# Shema_ele.net
KiCad netlist of a schematic drawn in Altium Designer
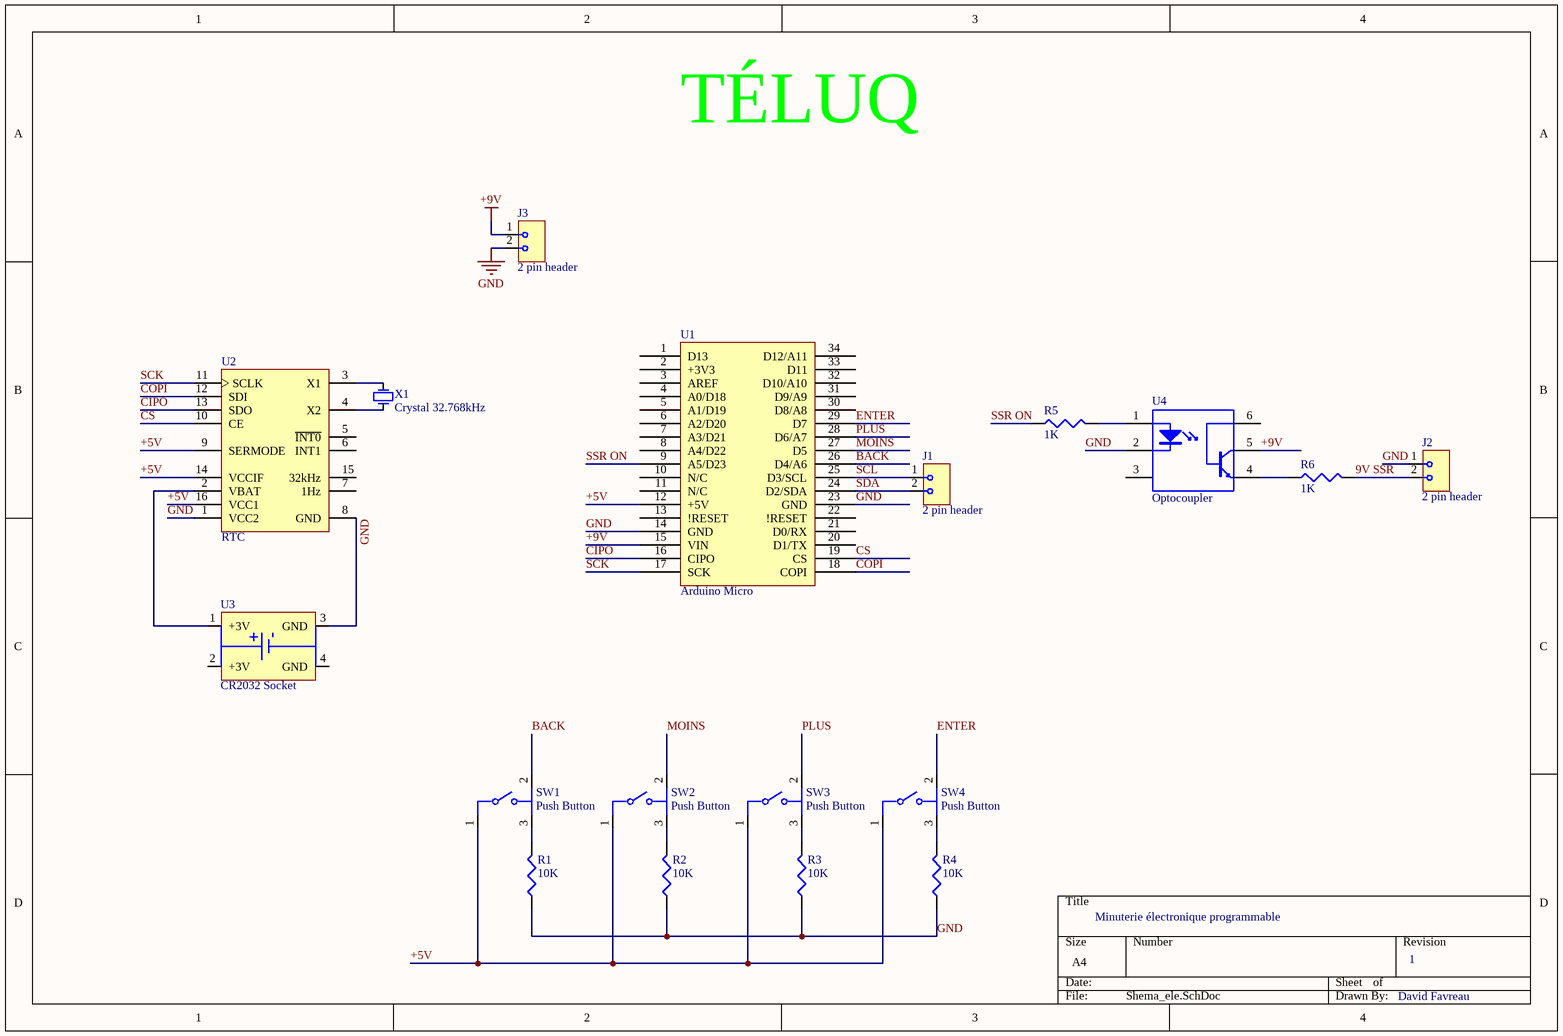
[diagram p0: Shema_ele.SchDoc]

(export (version "E")
  (design (tool "Eeschema 10.0.6"))
  (components
    (comp (ref "*")
      (value "Logo TELUQ")
      (footprint "Logo TELQUQ")
      (libsource (lib "Minuterie_SCH") (part "Logo TELUQ"))
    )
    (comp (ref "J1")
      (value "2 pin header")
      (footprint "Dual header")
      (description "2.54mm (0.1\") Pitch SIL Vertical PC Tail Pin Header, 6.1mm mating pin height, tin, 2 contacts")
      (fields (field (name "MANUFACTURER") "Harwin") (field (name "MANUFACTURER PART NUMBER") "M20-9990246"))
      (libsource (lib "Minuterie_SCH") (part "M20-9990246"))
    )
    (comp (ref "J2")
      (value "2 pin header")
      (footprint "Dual header")
      (description "2.54mm (0.1\") Pitch SIL Vertical PC Tail Pin Header, 6.1mm mating pin height, tin, 2 contacts")
      (fields (field (name "MANUFACTURER") "Harwin") (field (name "MANUFACTURER PART NUMBER") "M20-9990246"))
      (libsource (lib "Minuterie_SCH") (part "M20-9990246"))
    )
    (comp (ref "J3")
      (value "2 pin header")
      (footprint "Dual header")
      (description "2.54mm (0.1\") Pitch SIL Vertical PC Tail Pin Header, 6.1mm mating pin height, tin, 2 contacts")
      (fields (field (name "MANUFACTURER") "Harwin") (field (name "MANUFACTURER PART NUMBER") "M20-9990246"))
      (libsource (lib "Minuterie_SCH") (part "M20-9990246"))
    )
    (comp (ref "R1")
      (value "10K")
      (footprint "Res_TH")
      (description "Res Metal Film 10K Ohm 1% 1/4W ±100ppm/°C Conformal Axial Thru-Hole T/R")
      (fields
        (field (name "MANUFACTURER") "Yageo")
        (field (name "MANUFACTURER PART NUMBER") "MFR-25FRF52-10K")
      )
      (libsource (lib "Minuterie_SCH") (part "MFR-25FRF52-10K"))
    )
    (comp (ref "R2")
      (value "10K")
      (footprint "Res_TH")
      (description "Res Metal Film 10K Ohm 1% 1/4W ±100ppm/°C Conformal Axial Thru-Hole T/R")
      (fields
        (field (name "MANUFACTURER") "Yageo")
        (field (name "MANUFACTURER PART NUMBER") "MFR-25FRF52-10K")
      )
      (libsource (lib "Minuterie_SCH") (part "MFR-25FRF52-10K"))
    )
    (comp (ref "R3")
      (value "10K")
      (footprint "Res_TH")
      (description "Res Metal Film 10K Ohm 1% 1/4W ±100ppm/°C Conformal Axial Thru-Hole T/R")
      (fields
        (field (name "MANUFACTURER") "Yageo")
        (field (name "MANUFACTURER PART NUMBER") "MFR-25FRF52-10K")
      )
      (libsource (lib "Minuterie_SCH") (part "MFR-25FRF52-10K"))
    )
    (comp (ref "R4")
      (value "10K")
      (footprint "Res_TH")
      (description "Res Metal Film 10K Ohm 1% 1/4W ±100ppm/°C Conformal Axial Thru-Hole T/R")
      (fields
        (field (name "MANUFACTURER") "Yageo")
        (field (name "MANUFACTURER PART NUMBER") "MFR-25FRF52-10K")
      )
      (libsource (lib "Minuterie_SCH") (part "MFR-25FRF52-10K"))
    )
    (comp (ref "R5")
      (value "1K")
      (footprint "Res_TH")
      (description "Res Metal Film 1K Ohm 1% 0.25W(1/4W) ±100ppm/C AXL Automotive T/R")
      (fields
        (field (name "MANUFACTURER") "Yageo")
        (field (name "MANUFACTURER PART NUMBER") "MFR-25FRF52-1K")
      )
      (libsource (lib "Minuterie_SCH") (part "MFR-25FRF52-1K"))
    )
    (comp (ref "R6")
      (value "1K")
      (footprint "Res_TH")
      (description "Res Metal Film 1K Ohm 1% 0.25W(1/4W) ±100ppm/C AXL Automotive T/R")
      (fields
        (field (name "MANUFACTURER") "Yageo")
        (field (name "MANUFACTURER PART NUMBER") "MFR-25FRF52-1K")
      )
      (libsource (lib "Minuterie_SCH") (part "MFR-25FRF52-1K"))
    )
    (comp (ref "SW1")
      (value "Push Button")
      (footprint "Push button")
      (description "Switch Tactile OFF (ON) SPST Round Button PC Pins 0.05A 24VDC 1.57N Thru-Hole Loose")
      (fields
        (field (name "MANUFACTURER") "TE Connectivity Alcoswitch")
        (field (name "MANUFACTURER PART NUMBER") "FSM103")
      )
      (libsource (lib "Minuterie_SCH") (part "FSM103"))
    )
    (comp (ref "SW2")
      (value "Push Button")
      (footprint "Push button")
      (description "Switch Tactile OFF (ON) SPST Round Button PC Pins 0.05A 24VDC 1.57N Thru-Hole Loose")
      (fields
        (field (name "MANUFACTURER") "TE Connectivity Alcoswitch")
        (field (name "MANUFACTURER PART NUMBER") "FSM103")
      )
      (libsource (lib "Minuterie_SCH") (part "FSM103"))
    )
    (comp (ref "SW3")
      (value "Push Button")
      (footprint "Push button")
      (description "Switch Tactile OFF (ON) SPST Round Button PC Pins 0.05A 24VDC 1.57N Thru-Hole Loose")
      (fields
        (field (name "MANUFACTURER") "TE Connectivity Alcoswitch")
        (field (name "MANUFACTURER PART NUMBER") "FSM103")
      )
      (libsource (lib "Minuterie_SCH") (part "FSM103"))
    )
    (comp (ref "SW4")
      (value "Push Button")
      (footprint "Push button")
      (description "Switch Tactile OFF (ON) SPST Round Button PC Pins 0.05A 24VDC 1.57N Thru-Hole Loose")
      (fields
        (field (name "MANUFACTURER") "TE Connectivity Alcoswitch")
        (field (name "MANUFACTURER PART NUMBER") "FSM103")
      )
      (libsource (lib "Minuterie_SCH") (part "FSM103"))
    )
    (comp (ref "U1")
      (value "Arduino Micro")
      (footprint "Micro-C")
      (description "ATmega32u4 Microcontroller Micro Development Board 16MHz CPU 2.5KB RAM 1KB/32KB EEPROM/Flash")
      (fields (field (name "MANUFACTURER") "Arduino") (field (name "MANUFACTURER PART NUMBER") "A000053"))
      (libsource (lib "Minuterie_SCH") (part "A000053"))
    )
    (comp (ref "U2")
      (value "RTC")
      (footprint "DIP16")
      (description "DS1306 Series 2 to 5.5 V 96B Battery-Backed NV RAM Serial Alarm RTC - DIP-16")
      (fields (field (name "MANUFACTURER") "Maxim") (field (name "MANUFACTURER PART NUMBER") "DS1306N+"))
      (libsource (lib "Minuterie_SCH") (part "DS1306N+"))
    )
    (comp (ref "U3")
      (value "CR2032 Socket")
      (footprint "Battery socket")
      (description "Heyco RDD Lockit Strain Relief Bushings Straight-Thru RDD 101A BLACK")
      (fields
        (field (name "MANUFACTURER") "Adafruit Industries")
        (field (name "MANUFACTURER PART NUMBER") "1870")
      )
      (libsource (lib "Minuterie_SCH") (part "1870"))
    )
    (comp (ref "U4")
      (value "Optocoupler")
      (footprint "DIP6")
      (description "Single Channel 80 V 5000 Vrms Phototransistor Optocoupler Through Hole - DIP-6")
      (fields (field (name "MANUFACTURER") "Vishay") (field (name "MANUFACTURER PART NUMBER") "4N35"))
      (libsource (lib "Minuterie_SCH") (part "4N35"))
    )
    (comp (ref "X1")
      (value "Crystal 32.768kHz")
      (footprint "Crystal")
      (description "Crystal 0.032768MHz ±20ppm (Tol) 6pF Flexural 35000Ohm 2-Pin Thru-Hole Bulk")
      (fields
        (field (name "MANUFACTURER") "Citizen")
        (field (name "MANUFACTURER PART NUMBER") "CFS-20632768DZBB")
      )
      (libsource (lib "Minuterie_SCH") (part "CFS-20632768DZBB"))
    )
  )
  (nets
    (net (code "1") (name "+9V") (class "Default")
      (node (ref "J3") (pin "1") (pinfunction "1_1") (pintype "passive"))
      (node (ref "U1") (pin "15") (pinfunction "VIN_15") (pintype "passive"))
      (node (ref "U4") (pin "5") (pinfunction "C_5") (pintype "passive"))
    )
    (net (code "2") (name "/+5V") (class "Default")
      (node (ref "SW1") (pin "1") (pinfunction "1_1") (pintype "passive"))
      (node (ref "SW2") (pin "1") (pinfunction "1_1") (pintype "passive"))
      (node (ref "SW3") (pin "1") (pinfunction "1_1") (pintype "passive"))
      (node (ref "SW4") (pin "1") (pinfunction "1_1") (pintype "passive"))
      (node (ref "U1") (pin "12") (pinfunction "+5V_12") (pintype "passive"))
      (node (ref "U2") (pin "14") (pinfunction "VCCIF_14") (pintype "power_in"))
      (node (ref "U2") (pin "16") (pinfunction "VCC1_16") (pintype "power_in"))
      (node (ref "U2") (pin "9") (pinfunction "SERMODE_9") (pintype "passive"))
    )
    (net (code "3") (name "/9V SSR") (class "Default")
      (node (ref "J2") (pin "2") (pinfunction "2_2") (pintype "passive"))
      (node (ref "R6") (pin "2") (pinfunction "2_2") (pintype "passive"))
    )
    (net (code "5") (name "/BACK") (class "Default")
      (node (ref "SW1") (pin "2") (pinfunction "2_2") (pintype "passive"))
      (node (ref "U1") (pin "26") (pinfunction "D4/A6_26") (pintype "passive"))
    )
    (net (code "6") (name "/CIPO") (class "Default")
      (node (ref "U1") (pin "16") (pinfunction "CIPO_16") (pintype "passive"))
      (node (ref "U2") (pin "13") (pinfunction "SDO_13") (pintype "passive"))
    )
    (net (code "7") (name "/COPI") (class "Default")
      (node (ref "U1") (pin "18") (pinfunction "COPI_18") (pintype "passive"))
      (node (ref "U2") (pin "12") (pinfunction "SDI_12") (pintype "passive"))
    )
    (net (code "8") (name "/CS") (class "Default")
      (node (ref "U1") (pin "19") (pinfunction "CS_19") (pintype "passive"))
      (node (ref "U2") (pin "10") (pinfunction "CE_10") (pintype "passive"))
    )
    (net (code "9") (name "/ENTER") (class "Default")
      (node (ref "SW4") (pin "2") (pinfunction "2_2") (pintype "passive"))
      (node (ref "U1") (pin "29") (pinfunction "D7_29") (pintype "passive"))
    )
    (net (code "10") (name "/MOINS") (class "Default")
      (node (ref "SW2") (pin "2") (pinfunction "2_2") (pintype "passive"))
      (node (ref "U1") (pin "27") (pinfunction "D5_27") (pintype "passive"))
    )
    (net (code "11") (name "/PLUS") (class "Default")
      (node (ref "SW3") (pin "2") (pinfunction "2_2") (pintype "passive"))
      (node (ref "U1") (pin "28") (pinfunction "D6/A7_28") (pintype "passive"))
    )
    (net (code "12") (name "/SCK") (class "Default")
      (node (ref "U1") (pin "17") (pinfunction "SCK_17") (pintype "passive"))
      (node (ref "U2") (pin "11") (pinfunction "SCLK_11") (pintype "passive"))
    )
    (net (code "13") (name "/SCL") (class "Default")
      (node (ref "J1") (pin "1") (pinfunction "1_1") (pintype "passive"))
      (node (ref "U1") (pin "25") (pinfunction "D3/SCL_25") (pintype "passive"))
    )
    (net (code "14") (name "/SDA") (class "Default")
      (node (ref "J1") (pin "2") (pinfunction "2_2") (pintype "passive"))
      (node (ref "U1") (pin "24") (pinfunction "D2/SDA_24") (pintype "passive"))
    )
    (net (code "15") (name "/SSR ON") (class "Default")
      (node (ref "R5") (pin "1") (pinfunction "1_1") (pintype "passive"))
      (node (ref "U1") (pin "9") (pinfunction "A5/D23_9") (pintype "passive"))
    )
    (net (code "16") (name "GND") (class "Default")
      (node (ref "J2") (pin "1") (pinfunction "1_1") (pintype "passive"))
      (node (ref "J3") (pin "2") (pinfunction "2_2") (pintype "passive"))
      (node (ref "R1") (pin "1") (pinfunction "1_1") (pintype "passive"))
      (node (ref "R2") (pin "1") (pinfunction "1_1") (pintype "passive"))
      (node (ref "R3") (pin "1") (pinfunction "1_1") (pintype "passive"))
      (node (ref "R4") (pin "1") (pinfunction "1_1") (pintype "passive"))
      (node (ref "U1") (pin "14") (pinfunction "GND_14") (pintype "passive"))
      (node (ref "U1") (pin "23") (pinfunction "GND_23") (pintype "passive"))
      (node (ref "U2") (pin "1") (pinfunction "VCC2_1") (pintype "power_in"))
      (node (ref "U2") (pin "8") (pinfunction "GND_8") (pintype "power_in"))
      (node (ref "U3") (pin "3") (pinfunction "GND_3") (pintype "passive"))
      (node (ref "U4") (pin "2") (pinfunction "C_2") (pintype "passive"))
    )
    (net (code "17") (name "Net-(R1-Pad2)") (class "Default")
      (node (ref "R1") (pin "2") (pinfunction "2_2") (pintype "passive"))
      (node (ref "SW1") (pin "3") (pinfunction "3_3") (pintype "passive"))
    )
    (net (code "18") (name "Net-(R2-Pad2)") (class "Default")
      (node (ref "R2") (pin "2") (pinfunction "2_2") (pintype "passive"))
      (node (ref "SW2") (pin "3") (pinfunction "3_3") (pintype "passive"))
    )
    (net (code "19") (name "Net-(R3-Pad2)") (class "Default")
      (node (ref "R3") (pin "2") (pinfunction "2_2") (pintype "passive"))
      (node (ref "SW3") (pin "3") (pinfunction "3_3") (pintype "passive"))
    )
    (net (code "20") (name "Net-(R4-Pad2)") (class "Default")
      (node (ref "R4") (pin "2") (pinfunction "2_2") (pintype "passive"))
      (node (ref "SW4") (pin "3") (pinfunction "3_3") (pintype "passive"))
    )
    (net (code "21") (name "Net-(U2-VBAT)") (class "Default")
      (node (ref "U2") (pin "2") (pinfunction "VBAT_2") (pintype "power_in"))
      (node (ref "U3") (pin "1") (pinfunction "+3V_1") (pintype "passive"))
    )
    (net (code "22") (name "Net-(U2-X1)") (class "Default")
      (node (ref "U2") (pin "3") (pinfunction "X1_3") (pintype "passive"))
      (node (ref "X1") (pin "2") (pinfunction "X2_2") (pintype "passive"))
    )
    (net (code "23") (name "Net-(U2-X2)") (class "Default")
      (node (ref "U2") (pin "4") (pinfunction "X2_4") (pintype "passive"))
      (node (ref "X1") (pin "1") (pinfunction "X1_1") (pintype "passive"))
    )
    (net (code "24") (name "Net-(U4-A)") (class "Default")
      (node (ref "R5") (pin "2") (pinfunction "2_2") (pintype "passive"))
      (node (ref "U4") (pin "1") (pinfunction "A_1") (pintype "passive"))
    )
    (net (code "25") (name "Net-(U4-E)") (class "Default")
      (node (ref "R6") (pin "1") (pinfunction "1_1") (pintype "passive"))
      (node (ref "U4") (pin "4") (pinfunction "E_4") (pintype "passive"))
    )
    (net (code "26") (name "unconnected-(U1-!RESET-Pad13)") (class "Default")
      (node (ref "U1") (pin "13") (pinfunction "!RESET_13") (pintype "passive"))
    )
    (net (code "27") (name "unconnected-(U1-!RESET-Pad22)") (class "Default")
      (node (ref "U1") (pin "22") (pinfunction "!RESET_22") (pintype "passive"))
    )
    (net (code "28") (name "unconnected-(U1-+3V3-Pad2)") (class "Default")
      (node (ref "U1") (pin "2") (pinfunction "+3V3_2") (pintype "passive"))
    )
    (net (code "29") (name "unconnected-(U1-A0{slash}D18-Pad4)") (class "Default")
      (node (ref "U1") (pin "4") (pinfunction "A0/D18_4") (pintype "passive"))
    )
    (net (code "30") (name "unconnected-(U1-A1{slash}D19-Pad5)") (class "Default")
      (node (ref "U1") (pin "5") (pinfunction "A1/D19_5") (pintype "passive"))
    )
    (net (code "31") (name "unconnected-(U1-A2{slash}D20-Pad6)") (class "Default")
      (node (ref "U1") (pin "6") (pinfunction "A2/D20_6") (pintype "passive"))
    )
    (net (code "32") (name "unconnected-(U1-A3{slash}D21-Pad7)") (class "Default")
      (node (ref "U1") (pin "7") (pinfunction "A3/D21_7") (pintype "passive"))
    )
    (net (code "33") (name "unconnected-(U1-A4{slash}D22-Pad8)") (class "Default")
      (node (ref "U1") (pin "8") (pinfunction "A4/D22_8") (pintype "passive"))
    )
    (net (code "34") (name "unconnected-(U1-AREF-Pad3)") (class "Default")
      (node (ref "U1") (pin "3") (pinfunction "AREF_3") (pintype "passive"))
    )
    (net (code "35") (name "unconnected-(U1-D0{slash}RX-Pad21)") (class "Default")
      (node (ref "U1") (pin "21") (pinfunction "D0/RX_21") (pintype "passive"))
    )
    (net (code "36") (name "unconnected-(U1-D1{slash}TX-Pad20)") (class "Default")
      (node (ref "U1") (pin "20") (pinfunction "D1/TX_20") (pintype "passive"))
    )
    (net (code "37") (name "unconnected-(U1-D8{slash}A8-Pad30)") (class "Default")
      (node (ref "U1") (pin "30") (pinfunction "D8/A8_30") (pintype "passive"))
    )
    (net (code "38") (name "unconnected-(U1-D9{slash}A9-Pad31)") (class "Default")
      (node (ref "U1") (pin "31") (pinfunction "D9/A9_31") (pintype "passive"))
    )
    (net (code "39") (name "unconnected-(U1-D10{slash}A10-Pad32)") (class "Default")
      (node (ref "U1") (pin "32") (pinfunction "D10/A10_32") (pintype "passive"))
    )
    (net (code "40") (name "unconnected-(U1-D11-Pad33)") (class "Default")
      (node (ref "U1") (pin "33") (pinfunction "D11_33") (pintype "passive"))
    )
    (net (code "41") (name "unconnected-(U1-D12{slash}A11-Pad34)") (class "Default")
      (node (ref "U1") (pin "34") (pinfunction "D12/A11_34") (pintype "passive"))
    )
    (net (code "42") (name "unconnected-(U1-D13-Pad1)") (class "Default")
      (node (ref "U1") (pin "1") (pinfunction "D13_1") (pintype "passive"))
    )
    (net (code "43") (name "unconnected-(U1-N{slash}C-Pad10)") (class "Default")
      (node (ref "U1") (pin "10") (pinfunction "N/C_10") (pintype "passive"))
    )
    (net (code "44") (name "unconnected-(U1-N{slash}C-Pad11)") (class "Default")
      (node (ref "U1") (pin "11") (pinfunction "N/C_11") (pintype "passive"))
    )
    (net (code "45") (name "unconnected-(U2-1Hz-Pad7)") (class "Default")
      (node (ref "U2") (pin "7") (pinfunction "1Hz_7") (pintype "open_collector"))
    )
    (net (code "46") (name "unconnected-(U2-32kHz-Pad15)") (class "Default")
      (node (ref "U2") (pin "15") (pinfunction "32kHz_15") (pintype "passive"))
    )
    (net (code "47") (name "unconnected-(U2-INT1-Pad6)") (class "Default")
      (node (ref "U2") (pin "6") (pinfunction "INT1_6") (pintype "passive"))
    )
    (net (code "48") (name "unconnected-(U2-~{INT0}-Pad5)") (class "Default")
      (node (ref "U2") (pin "5") (pinfunction "~{INT0}_5") (pintype "open_collector"))
    )
    (net (code "49") (name "unconnected-(U3-+3V-Pad2)") (class "Default")
      (node (ref "U3") (pin "2") (pinfunction "+3V_2") (pintype "passive"))
    )
    (net (code "50") (name "unconnected-(U3-GND-Pad4)") (class "Default")
      (node (ref "U3") (pin "4") (pinfunction "GND_4") (pintype "passive"))
    )
    (net (code "51") (name "unconnected-(U4-B-Pad6)") (class "Default")
      (node (ref "U4") (pin "6") (pinfunction "B_6") (pintype "passive"))
    )
    (net (code "52") (name "unconnected-(U4-NC-Pad3)") (class "Default")
      (node (ref "U4") (pin "3") (pinfunction "NC_3") (pintype "passive"))
    )
  )
)
